# to-pcb.net
KiCad netlist of a schematic drawn in EAGLE
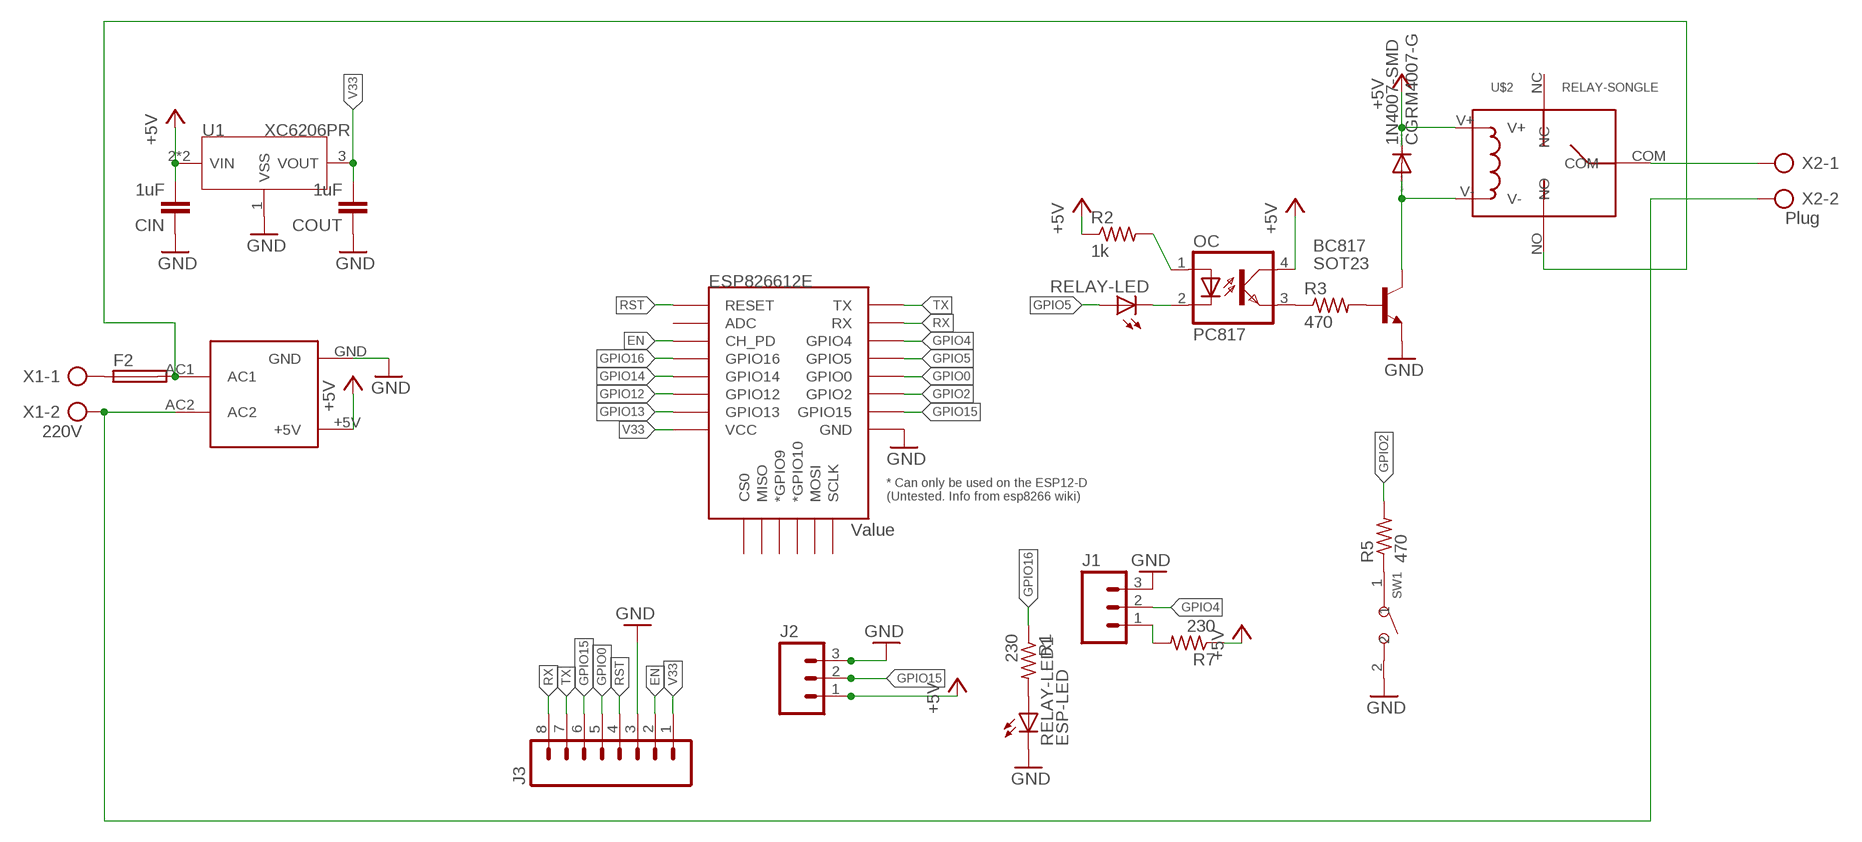
[diagram p0: schematic, sheet 1]

(export (version "E")
  (design (tool "Eeschema 10.0.6"))
  (components
    (comp (ref "1N4007-SMD")
      (value "CGRM4007-G")
      (footprint "eagle-import:SOD-123_MINI-SMA")
      (libsource (lib "eagle-import") (part "CGRM400-G7"))
    )
    (comp (ref "BC817")
      (value "SOT23")
      (footprint "eagle-import:SOT23-BEC")
      (libsource (lib "eagle-import") (part "-NPN-SOT23-BECBC817"))
    )
    (comp (ref "CIN")
      (value "1uF")
      (footprint "eagle-import:C0805")
      (libsource (lib "eagle-import") (part "C-EUC0805"))
    )
    (comp (ref "COUT")
      (value "1uF")
      (footprint "eagle-import:C0805")
      (libsource (lib "eagle-import") (part "C-EUC0805"))
    )
    (comp (ref "ESP826612E")
      (value "Value")
      (footprint "eagle-import:ESP12E-SMD")
      (libsource (lib "eagle-import") (part "ESP12ESMD"))
    )
    (comp (ref "F2")
      (value "TR5")
      (footprint "eagle-import:TR5")
      (libsource (lib "eagle-import") (part "TR5"))
    )
    (comp (ref "J1")
      (value "M03PTH")
      (footprint "eagle-import:1X03")
      (libsource (lib "eagle-import") (part "M03PTH"))
    )
    (comp (ref "J2")
      (value "M03PTH")
      (footprint "eagle-import:1X03")
      (libsource (lib "eagle-import") (part "M03PTH"))
    )
    (comp (ref "J3")
      (value "M08")
      (footprint "eagle-import:1X08_ROUND")
      (libsource (lib "eagle-import") (part "M08"))
    )
    (comp (ref "OC")
      (value "PC817")
      (footprint "eagle-import:DIL04")
      (fields (field (name "MPN") "PC817X4J000F"))
      (libsource (lib "eagle-import") (part "PC817"))
    )
    (comp (ref "R1")
      (value "230")
      (footprint "eagle-import:M0805")
      (libsource (lib "eagle-import") (part "R-US_M0805"))
    )
    (comp (ref "R2")
      (value "1k")
      (footprint "eagle-import:M0805")
      (libsource (lib "eagle-import") (part "R-US_M0805"))
    )
    (comp (ref "R3")
      (value "470")
      (footprint "eagle-import:M0805")
      (libsource (lib "eagle-import") (part "R-US_M0805"))
    )
    (comp (ref "R5")
      (value "470")
      (footprint "eagle-import:M0805")
      (libsource (lib "eagle-import") (part "R-US_M0805"))
    )
    (comp (ref "R7")
      (value "230")
      (footprint "eagle-import:M0805")
      (libsource (lib "eagle-import") (part "R-US_M0805"))
    )
    (comp (ref "RELAY-LED")
      (value "LEDCHIPLED_0805")
      (footprint "eagle-import:CHIPLED_0805")
      (libsource (lib "eagle-import") (part "LEDCHIPLED_0805"))
    )
    (comp (ref "RELAY-LED1")
      (value "ESP-LED")
      (footprint "eagle-import:CHIPLED_0805")
      (libsource (lib "eagle-import") (part "LEDCHIPLED_0805"))
    )
    (comp (ref "SW1")
      (value "DIP-BUTTON(2P-6.0X3.0X4.3MM)-TS-1101F")
      (footprint "eagle-import:SW2-5.0-6.0X3.0X4.3MM")
      (libsource (lib "eagle-import") (part "DIP-BUTTON(2P-6.0X3.0X4.3MM)-TS-1101F"))
    )
    (comp (ref "U$1")
      (value "HLK-PM01")
      (footprint "eagle-import:HLK-PM01")
      (libsource (lib "eagle-import") (part "HLK-PM01"))
    )
    (comp (ref "U$2")
      (value "RELAY-SONGLE")
      (footprint "eagle-import:RELAY-SONGLE")
      (libsource (lib "eagle-import") (part "RELAY-SONGLE"))
    )
    (comp (ref "U1")
      (value "XC6206PR")
      (footprint "eagle-import:SOT89")
      (libsource (lib "eagle-import") (part "XC6206PR"))
    )
    (comp (ref "X1")
      (value "220V")
      (footprint "eagle-import:AK300_2")
      (libsource (lib "eagle-import") (part "AK300/2"))
    )
    (comp (ref "X2")
      (value "Plug")
      (footprint "eagle-import:AK300_2")
      (libsource (lib "eagle-import") (part "AK300/2"))
    )
  )
  (nets
    (net (code "1") (name "+5V") (class "Default")
      (node (ref "1N4007-SMD") (pin "C") (pinfunction "C_C") (pintype "passive"))
      (node (ref "CIN") (pin "2") (pinfunction "2_2") (pintype "passive"))
      (node (ref "J2") (pin "1") (pinfunction "1_1") (pintype "passive"))
      (node (ref "OC") (pin "4") (pinfunction "COL_4") (pintype "passive"))
      (node (ref "R2") (pin "1") (pinfunction "1_1") (pintype "passive"))
      (node (ref "R7") (pin "1") (pinfunction "1_1") (pintype "passive"))
      (node (ref "U$1") (pin "+5V") (pinfunction "+5V_+5V") (pintype "bidirectional"))
      (node (ref "U$2") (pin "V+") (pinfunction "V+_V+") (pintype "bidirectional"))
      (node (ref "U1") (pin "2") (pinfunction "VIN_2") (pintype "input"))
      (node (ref "U1") (pin "4") (pinfunction "VIN_4") (pintype "input"))
    )
    (net (code "2") (name "EN") (class "Default")
      (node (ref "ESP826612E") (pin "CH_PD") (pinfunction "CH_PD_CH_PD") (pintype "bidirectional"))
      (node (ref "J3") (pin "2") (pinfunction "2_2") (pintype "passive"))
    )
    (net (code "3") (name "GND") (class "Default")
      (node (ref "BC817") (pin "E") (pinfunction "E_E") (pintype "passive"))
      (node (ref "CIN") (pin "1") (pinfunction "1_1") (pintype "passive"))
      (node (ref "COUT") (pin "1") (pinfunction "1_1") (pintype "passive"))
      (node (ref "ESP826612E") (pin "GND") (pinfunction "GND_GND") (pintype "bidirectional"))
      (node (ref "J1") (pin "3") (pinfunction "3_3") (pintype "passive"))
      (node (ref "J2") (pin "3") (pinfunction "3_3") (pintype "passive"))
      (node (ref "J3") (pin "3") (pinfunction "3_3") (pintype "passive"))
      (node (ref "RELAY-LED1") (pin "C") (pinfunction "C_C") (pintype "passive"))
      (node (ref "SW1") (pin "2") (pinfunction "2_2") (pintype "bidirectional"))
      (node (ref "U$1") (pin "GND") (pinfunction "GND_GND") (pintype "bidirectional"))
      (node (ref "U1") (pin "1") (pinfunction "VSS_1") (pintype "power_in"))
    )
    (net (code "4") (name "GPIO0") (class "Default")
      (node (ref "ESP826612E") (pin "GPIO0") (pinfunction "GPIO0_GPIO0") (pintype "bidirectional"))
      (node (ref "J3") (pin "5") (pinfunction "5_5") (pintype "passive"))
    )
    (net (code "5") (name "GPIO2") (class "Default")
      (node (ref "ESP826612E") (pin "GPIO2") (pinfunction "GPIO2_GPIO2") (pintype "bidirectional"))
      (node (ref "R5") (pin "2") (pinfunction "2_2") (pintype "passive"))
    )
    (net (code "6") (name "GPIO4") (class "Default")
      (node (ref "ESP826612E") (pin "GPIO4") (pinfunction "GPIO4_GPIO4") (pintype "bidirectional"))
      (node (ref "J1") (pin "2") (pinfunction "2_2") (pintype "passive"))
    )
    (net (code "7") (name "GPIO5") (class "Default")
      (node (ref "ESP826612E") (pin "GPIO5") (pinfunction "GPIO5_GPIO5") (pintype "bidirectional"))
      (node (ref "RELAY-LED") (pin "A") (pinfunction "A_A") (pintype "passive"))
    )
    (net (code "8") (name "GPIO12") (class "Default")
      (node (ref "ESP826612E") (pin "GPIO12") (pinfunction "GPIO12_GPIO12") (pintype "bidirectional"))
    )
    (net (code "9") (name "GPIO13") (class "Default")
      (node (ref "ESP826612E") (pin "GPIO13") (pinfunction "GPIO13_GPIO13") (pintype "bidirectional"))
    )
    (net (code "10") (name "GPIO14") (class "Default")
      (node (ref "ESP826612E") (pin "GPIO14") (pinfunction "GPIO14_GPIO14") (pintype "bidirectional"))
    )
    (net (code "11") (name "GPIO15") (class "Default")
      (node (ref "ESP826612E") (pin "GPIO15") (pinfunction "GPIO15_GPIO15") (pintype "bidirectional"))
      (node (ref "J2") (pin "2") (pinfunction "2_2") (pintype "passive"))
      (node (ref "J3") (pin "6") (pinfunction "6_6") (pintype "passive"))
    )
    (net (code "12") (name "GPIO16") (class "Default")
      (node (ref "ESP826612E") (pin "GPIO16") (pinfunction "GPIO16_GPIO16") (pintype "bidirectional"))
      (node (ref "R1") (pin "1") (pinfunction "1_1") (pintype "passive"))
    )
    (net (code "13") (name "Net-(1N4007-SMD-PadA)") (class "Default")
      (node (ref "1N4007-SMD") (pin "A") (pinfunction "A_A") (pintype "passive"))
      (node (ref "BC817") (pin "C") (pinfunction "C_C") (pintype "passive"))
      (node (ref "U$2") (pin "V-") (pinfunction "V-_V-") (pintype "bidirectional"))
    )
    (net (code "14") (name "Net-(BC817-PadB)") (class "Default")
      (node (ref "BC817") (pin "B") (pinfunction "B_B") (pintype "passive"))
      (node (ref "R3") (pin "2") (pinfunction "2_2") (pintype "passive"))
    )
    (net (code "15") (name "Net-(F2-Pad2)") (class "Default")
      (node (ref "F2") (pin "2") (pinfunction "2_2") (pintype "passive"))
      (node (ref "U$1") (pin "AC1") (pinfunction "AC1_AC1") (pintype "bidirectional"))
      (node (ref "U$2") (pin "NO") (pinfunction "NO_NO") (pintype "bidirectional"))
    )
    (net (code "16") (name "Net-(J1-Pad1)") (class "Default")
      (node (ref "J1") (pin "1") (pinfunction "1_1") (pintype "passive"))
      (node (ref "R7") (pin "2") (pinfunction "2_2") (pintype "passive"))
    )
    (net (code "17") (name "Net-(OC-A)") (class "Default")
      (node (ref "OC") (pin "1") (pinfunction "A_1") (pintype "passive"))
      (node (ref "R2") (pin "2") (pinfunction "2_2") (pintype "passive"))
    )
    (net (code "18") (name "Net-(OC-C)") (class "Default")
      (node (ref "OC") (pin "2") (pinfunction "C_2") (pintype "passive"))
      (node (ref "RELAY-LED") (pin "C") (pinfunction "C_C") (pintype "passive"))
    )
    (net (code "19") (name "Net-(OC-EMIT)") (class "Default")
      (node (ref "OC") (pin "3") (pinfunction "EMIT_3") (pintype "passive"))
      (node (ref "R3") (pin "1") (pinfunction "1_1") (pintype "passive"))
    )
    (net (code "20") (name "Net-(R1-Pad2)") (class "Default")
      (node (ref "R1") (pin "2") (pinfunction "2_2") (pintype "passive"))
      (node (ref "RELAY-LED1") (pin "A") (pinfunction "A_A") (pintype "passive"))
    )
    (net (code "21") (name "Net-(R5-Pad1)") (class "Default")
      (node (ref "R5") (pin "1") (pinfunction "1_1") (pintype "passive"))
      (node (ref "SW1") (pin "1") (pinfunction "1_1") (pintype "bidirectional"))
    )
    (net (code "22") (name "Net-(X1A-KL)") (class "Default")
      (node (ref "F2") (pin "1") (pinfunction "1_1") (pintype "passive"))
      (node (ref "X1") (pin "1") (pinfunction "KL_1") (pintype "passive"))
    )
    (net (code "23") (name "Net-(X1B-KL)") (class "Default")
      (node (ref "U$1") (pin "AC2") (pinfunction "AC2_AC2") (pintype "bidirectional"))
      (node (ref "X1") (pin "2") (pinfunction "KL_2") (pintype "passive"))
      (node (ref "X2") (pin "2") (pinfunction "KL_2") (pintype "passive"))
    )
    (net (code "24") (name "Net-(X2A-KL)") (class "Default")
      (node (ref "U$2") (pin "COM") (pinfunction "COM_COM") (pintype "bidirectional"))
      (node (ref "X2") (pin "1") (pinfunction "KL_1") (pintype "passive"))
    )
    (net (code "25") (name "RST") (class "Default")
      (node (ref "ESP826612E") (pin "RESET") (pinfunction "RESET_RESET") (pintype "bidirectional"))
      (node (ref "J3") (pin "4") (pinfunction "4_4") (pintype "passive"))
    )
    (net (code "26") (name "RX") (class "Default")
      (node (ref "ESP826612E") (pin "RXD0") (pinfunction "RX_RXD0") (pintype "bidirectional"))
      (node (ref "J3") (pin "8") (pinfunction "8_8") (pintype "passive"))
    )
    (net (code "27") (name "TX") (class "Default")
      (node (ref "ESP826612E") (pin "TXD0") (pinfunction "TX_TXD0") (pintype "bidirectional"))
      (node (ref "J3") (pin "7") (pinfunction "7_7") (pintype "passive"))
    )
    (net (code "28") (name "V33") (class "Default")
      (node (ref "COUT") (pin "2") (pinfunction "2_2") (pintype "passive"))
      (node (ref "ESP826612E") (pin "VCC") (pinfunction "VCC_VCC") (pintype "bidirectional"))
      (node (ref "J3") (pin "1") (pinfunction "1_1") (pintype "passive"))
      (node (ref "U1") (pin "3") (pinfunction "VOUT_3") (pintype "output"))
    )
    (net (code "29") (name "unconnected-(ESP826612E-*GPIO9-PadGPIO9)") (class "Default")
      (node (ref "ESP826612E") (pin "GPIO9") (pinfunction "*GPIO9_GPIO9") (pintype "bidirectional"))
    )
    (net (code "30") (name "unconnected-(ESP826612E-*GPIO10-PadGPIO10)") (class "Default")
      (node (ref "ESP826612E") (pin "GPIO10") (pinfunction "*GPIO10_GPIO10") (pintype "bidirectional"))
    )
    (net (code "31") (name "unconnected-(ESP826612E-PadADC)") (class "Default")
      (node (ref "ESP826612E") (pin "ADC") (pinfunction "ADC_ADC") (pintype "bidirectional"))
    )
    (net (code "32") (name "unconnected-(ESP826612E-PadCS0)") (class "Default")
      (node (ref "ESP826612E") (pin "CS0") (pinfunction "CS0_CS0") (pintype "bidirectional"))
    )
    (net (code "33") (name "unconnected-(ESP826612E-PadMISO)") (class "Default")
      (node (ref "ESP826612E") (pin "MISO") (pinfunction "MISO_MISO") (pintype "bidirectional"))
    )
    (net (code "34") (name "unconnected-(ESP826612E-PadMOSI)") (class "Default")
      (node (ref "ESP826612E") (pin "MOSI") (pinfunction "MOSI_MOSI") (pintype "bidirectional"))
    )
    (net (code "35") (name "unconnected-(ESP826612E-PadSCLK)") (class "Default")
      (node (ref "ESP826612E") (pin "SCLK") (pinfunction "SCLK_SCLK") (pintype "bidirectional"))
    )
    (net (code "36") (name "unconnected-(U$2-PadNC)") (class "Default")
      (node (ref "U$2") (pin "NC") (pinfunction "NC_NC") (pintype "bidirectional"))
    )
  )
)
